# AUX_CONNECTOR.net
KiCad netlist of a schematic drawn in Altium Designer
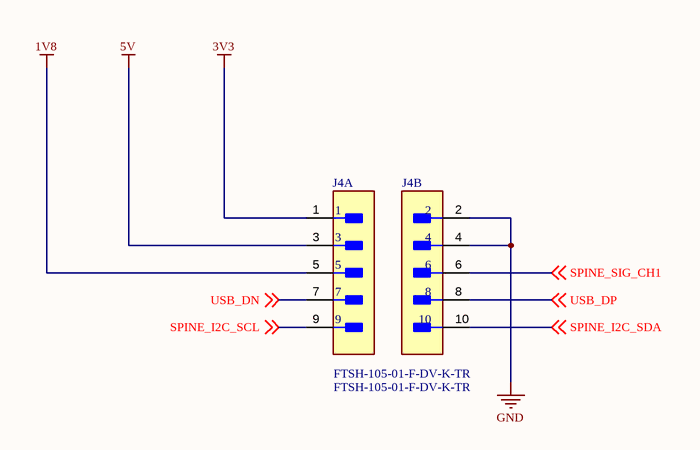
[diagram p0: AUX_CONNECTOR.SchDoc]

(export (version "E")
  (design (tool "Eeschema 10.0.6"))
  (components
    (comp (ref "J4")
      (value "FTSH-105-01-F-DV-K-TR")
      (footprint "FP-FTSH-105-01-F-DV-K-TR-MFG")
      (description "CONN HEADER SMD 10POS 1.27MM")
      (libsource (lib "Altium Content Vault") (part "544f42128f4185dcb88ce1ce9bf1982"))
    )
  )
  (nets
    (net (code "1") (name "1V8") (class "Default")
      (node (ref "J4") (pin "5") (pinfunction "5_5") (pintype "passive"))
    )
    (net (code "2") (name "3V3") (class "Default")
      (node (ref "J4") (pin "1") (pinfunction "1_1") (pintype "passive"))
    )
    (net (code "3") (name "5V") (class "Default")
      (node (ref "J4") (pin "3") (pinfunction "3_3") (pintype "passive"))
    )
    (net (code "4") (name "GND") (class "Default")
      (node (ref "J4") (pin "2") (pinfunction "2_2") (pintype "passive"))
      (node (ref "J4") (pin "4") (pinfunction "4_4") (pintype "passive"))
    )
    (net (code "5") (name "SPINE_I2C_SCL") (class "Default")
      (node (ref "J4") (pin "9") (pinfunction "9_9") (pintype "passive"))
    )
    (net (code "6") (name "SPINE_I2C_SDA") (class "Default")
      (node (ref "J4") (pin "10") (pinfunction "10_10") (pintype "passive"))
    )
    (net (code "7") (name "SPINE_SIG_CH1") (class "Default")
      (node (ref "J4") (pin "6") (pinfunction "6_6") (pintype "passive"))
    )
    (net (code "8") (name "USB_DN") (class "Default")
      (node (ref "J4") (pin "7") (pinfunction "7_7") (pintype "passive"))
    )
    (net (code "9") (name "USB_DP") (class "Default")
      (node (ref "J4") (pin "8") (pinfunction "8_8") (pintype "passive"))
    )
  )
)
